# Photobooth-RasPI-Controller.net
KiCad netlist of a schematic drawn in EAGLE
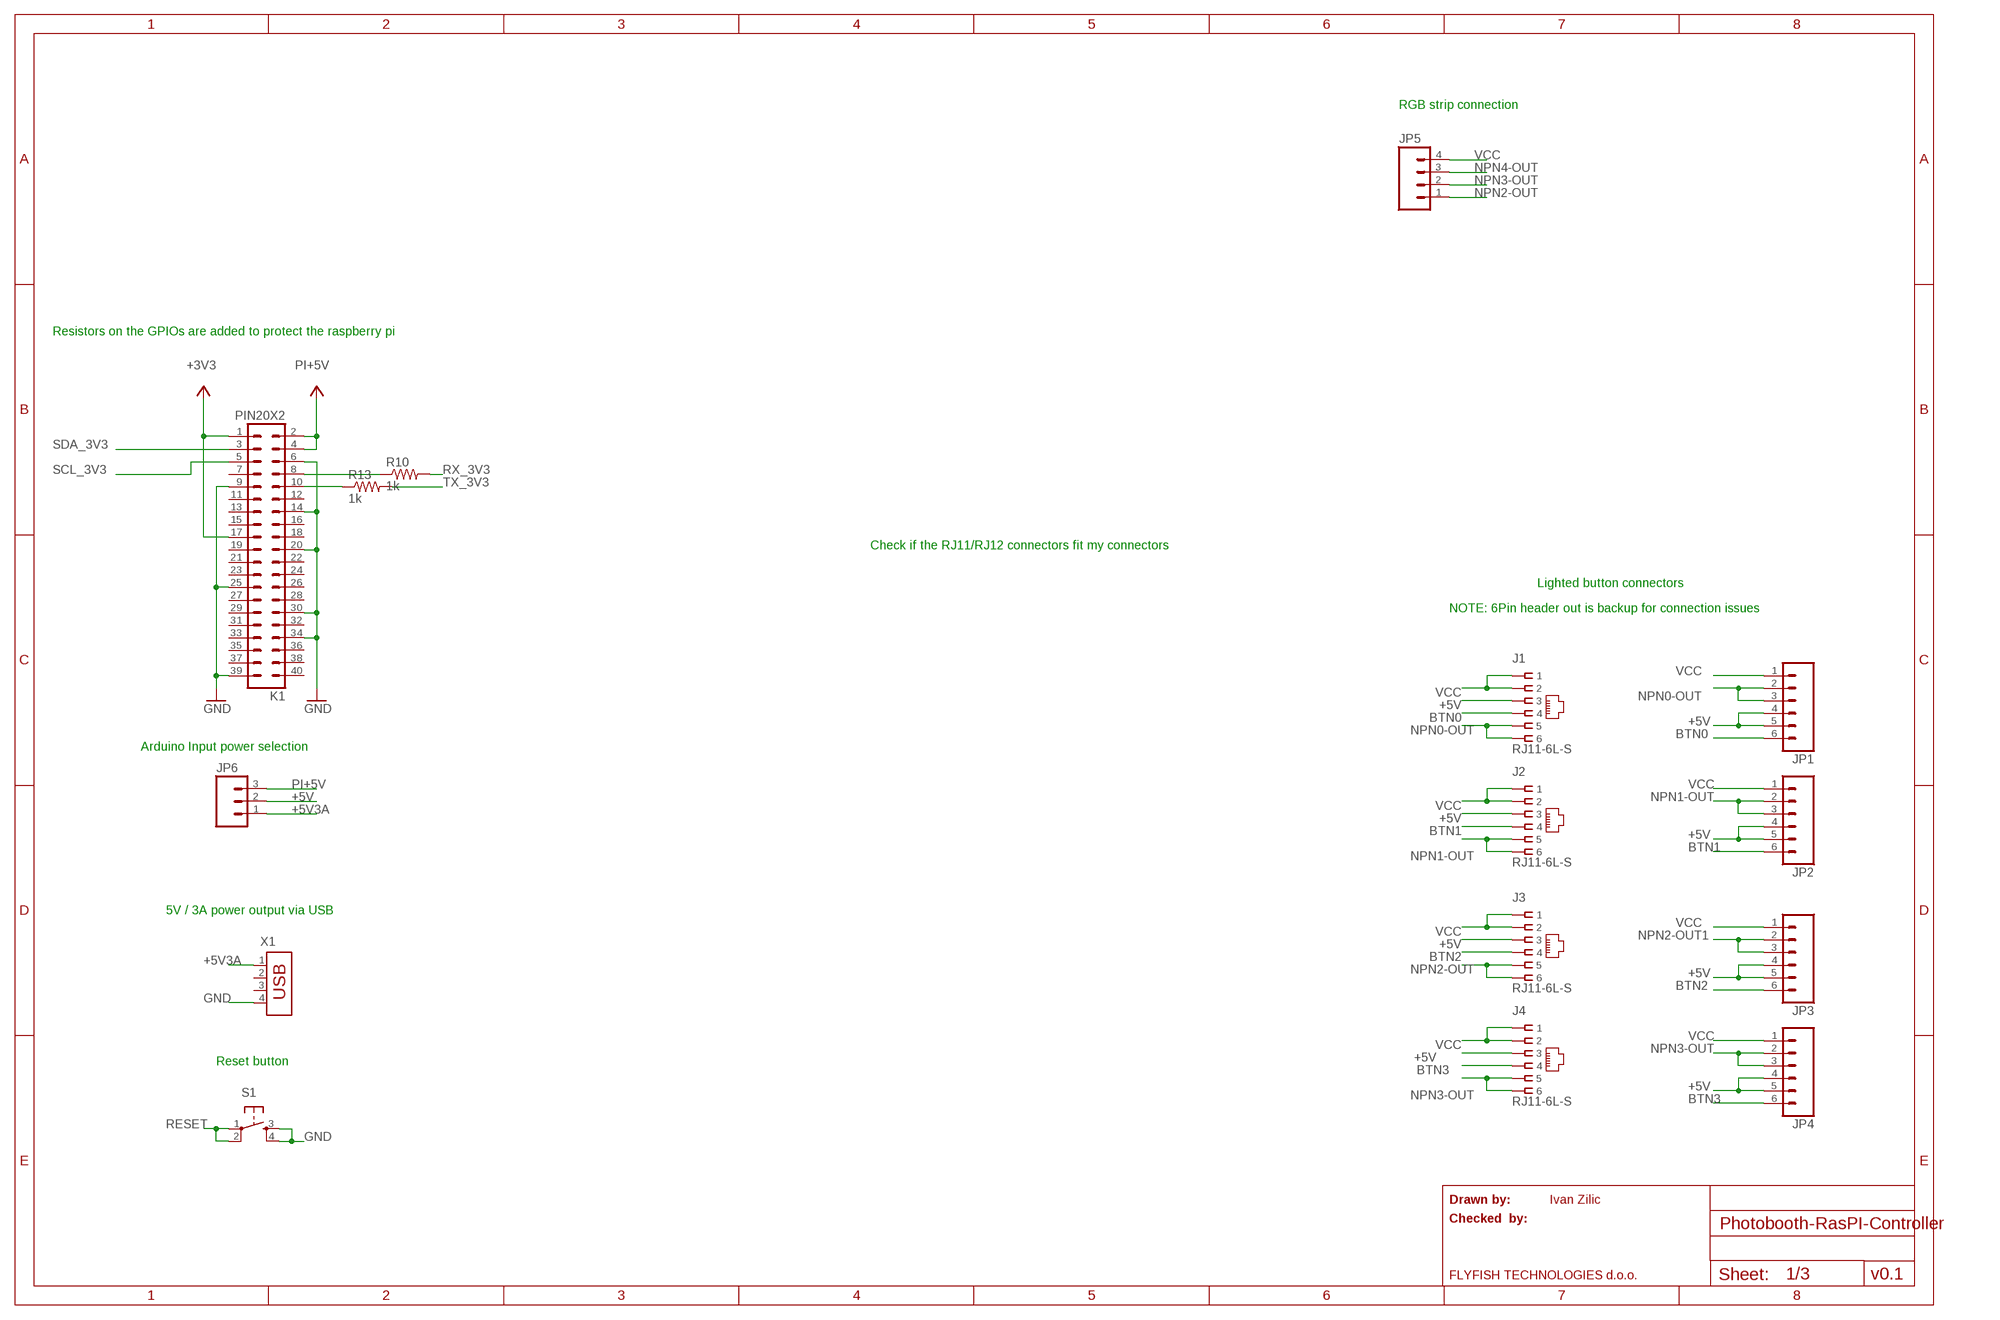
[diagram p0: schematic, sheet 1]
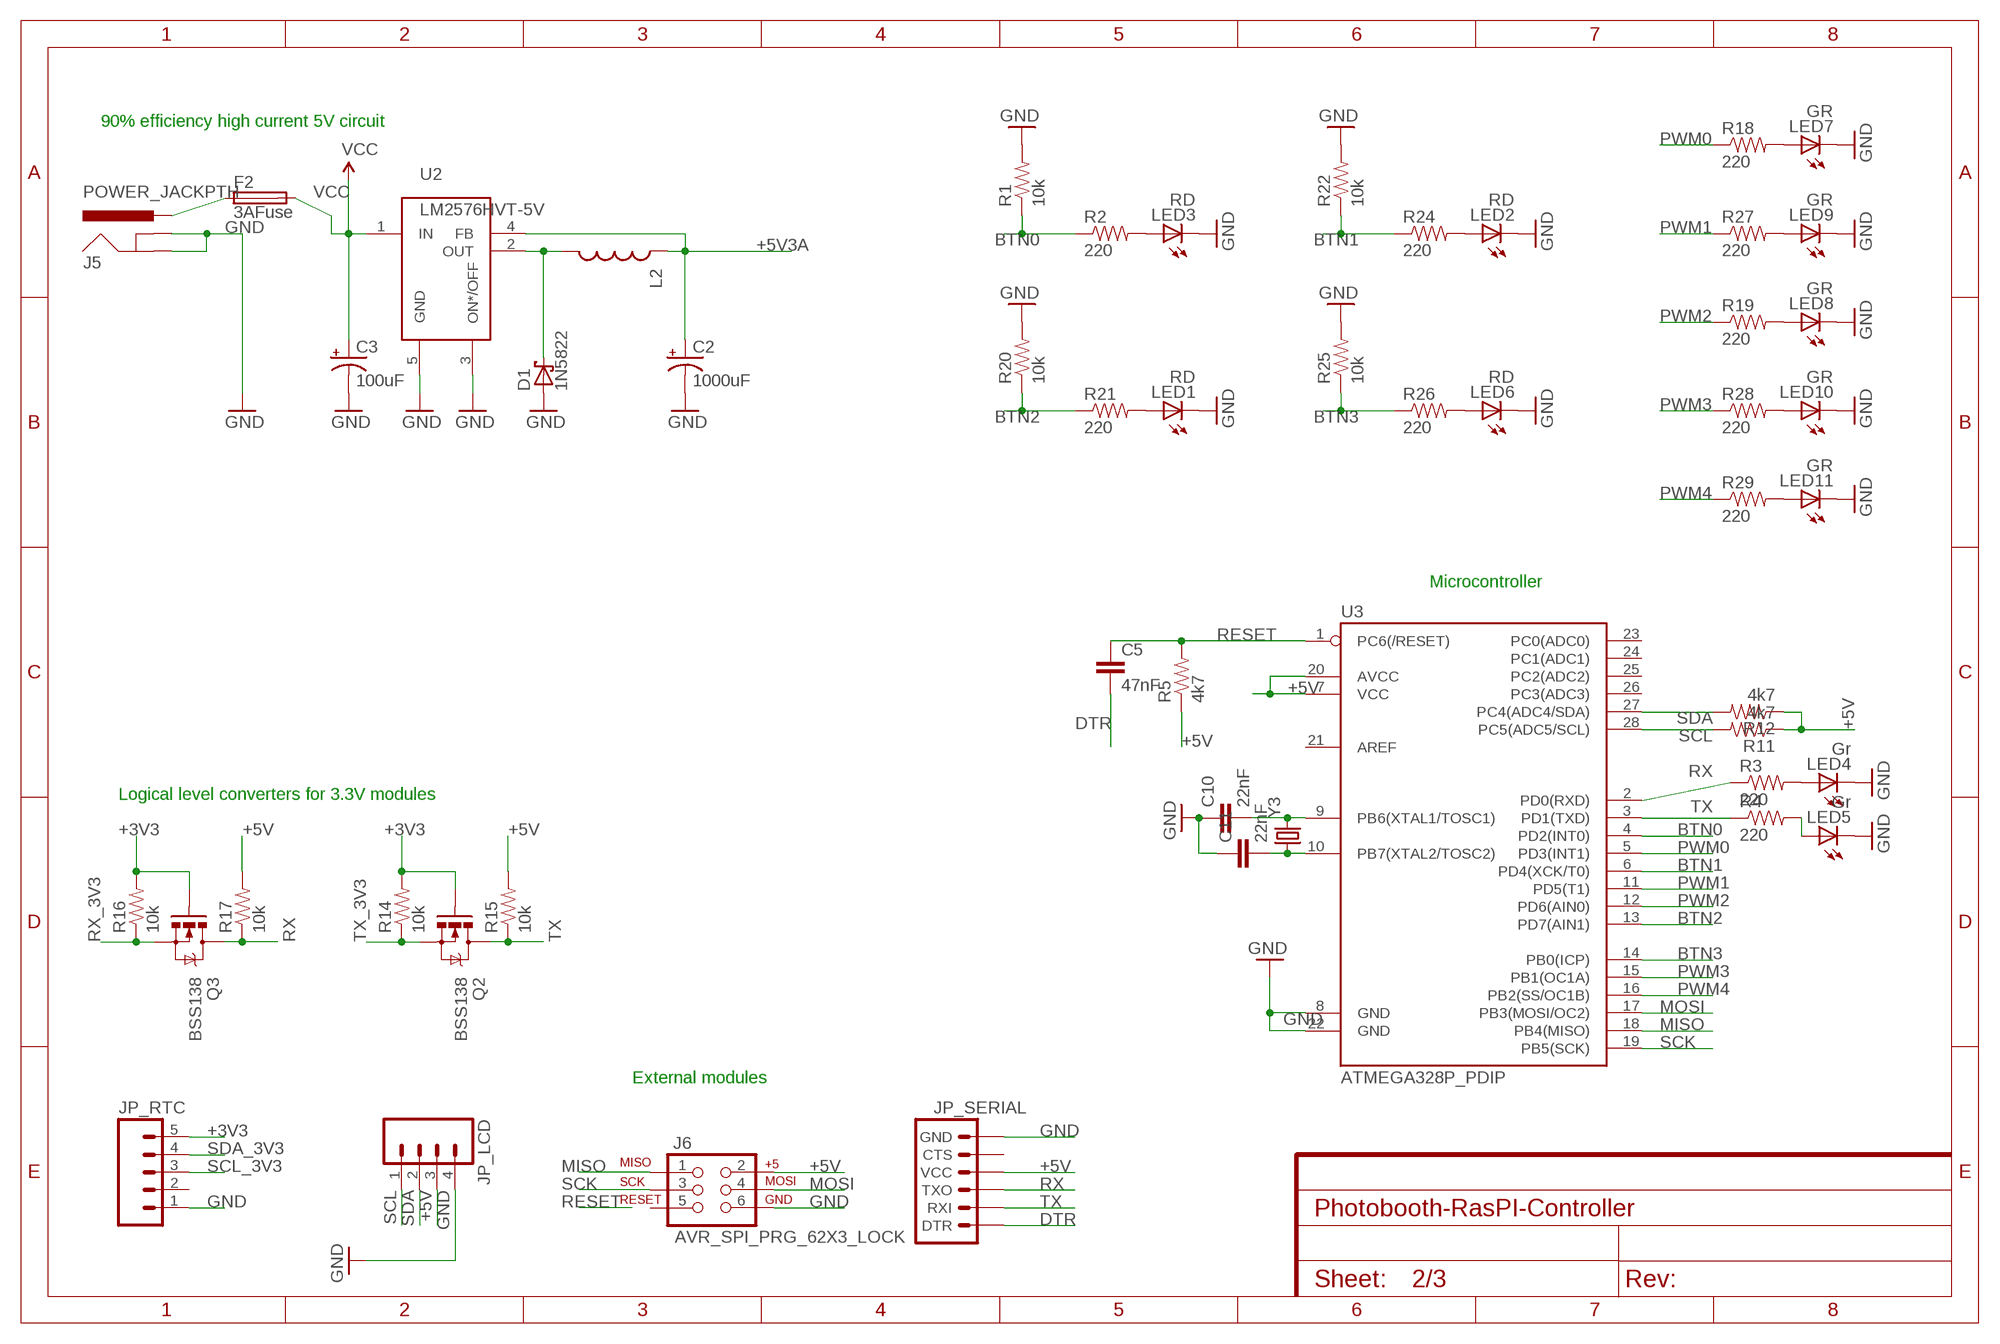
[diagram p1: schematic, sheet 2]
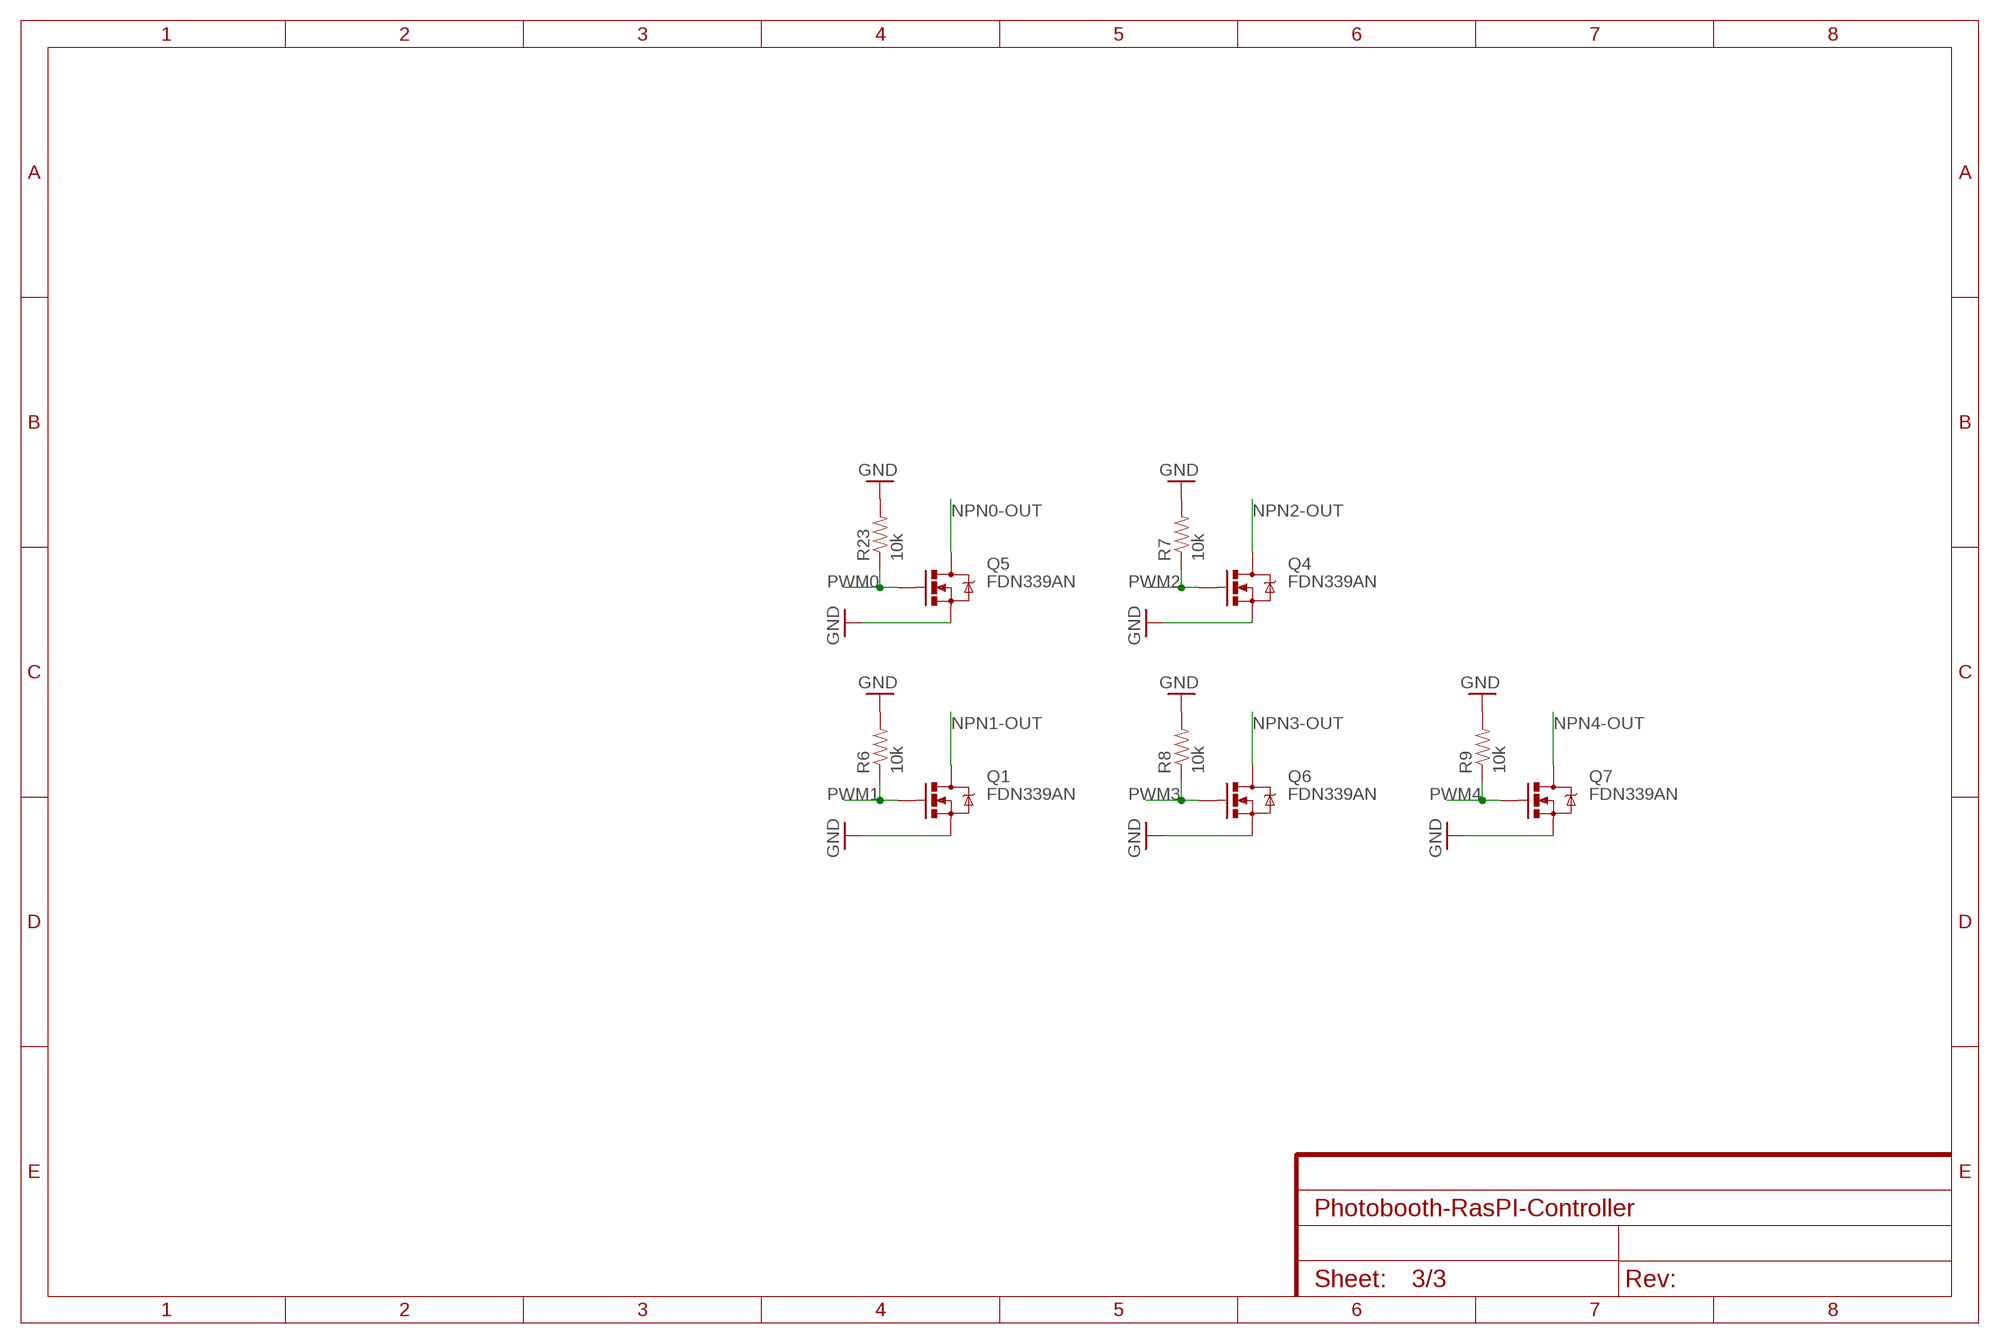
[diagram p2: schematic, sheet 3]

(export (version "E")
  (design (tool "Eeschema 10.0.6"))
  (components
    (comp (ref "Q1")
      (value "FDN339AN")
      (footprint "eagle-import:SOT23-3")
      (libsource (lib "eagle-import") (part "MOSFET-NCHANNELBSS138"))
    )
    (comp (ref "Q4")
      (value "FDN339AN")
      (footprint "eagle-import:SOT23-3")
      (libsource (lib "eagle-import") (part "MOSFET-NCHANNELBSS138"))
    )
    (comp (ref "Q5")
      (value "FDN339AN")
      (footprint "eagle-import:SOT23-3")
      (libsource (lib "eagle-import") (part "MOSFET-NCHANNELBSS138"))
    )
    (comp (ref "Q6")
      (value "FDN339AN")
      (footprint "eagle-import:SOT23-3")
      (libsource (lib "eagle-import") (part "MOSFET-NCHANNELBSS138"))
    )
    (comp (ref "Q7")
      (value "FDN339AN")
      (footprint "eagle-import:SOT23-3")
      (libsource (lib "eagle-import") (part "MOSFET-NCHANNELBSS138"))
    )
    (comp (ref "R6")
      (value "10k")
      (footprint "eagle-import:0805")
      (libsource (lib "eagle-import") (part "RESISTOR0805-RES"))
    )
    (comp (ref "R7")
      (value "10k")
      (footprint "eagle-import:0805")
      (libsource (lib "eagle-import") (part "RESISTOR0805-RES"))
    )
    (comp (ref "R8")
      (value "10k")
      (footprint "eagle-import:0805")
      (libsource (lib "eagle-import") (part "RESISTOR0805-RES"))
    )
    (comp (ref "R9")
      (value "10k")
      (footprint "eagle-import:0805")
      (libsource (lib "eagle-import") (part "RESISTOR0805-RES"))
    )
    (comp (ref "R23")
      (value "10k")
      (footprint "eagle-import:0805")
      (libsource (lib "eagle-import") (part "RESISTOR0805-RES"))
    )
    (comp (ref "J1")
      (value "RJ11-6L-S")
      (footprint "eagle-import:RJ11-NO_SHIELD")
      (fields (field (name "MF") "TYCO ELECTRONICS"))
      (libsource (lib "eagle-import") (part "RJ11-6L-S"))
    )
    (comp (ref "J2")
      (value "RJ11-6L-S")
      (footprint "eagle-import:RJ11-NO_SHIELD")
      (fields (field (name "MF") "TYCO ELECTRONICS"))
      (libsource (lib "eagle-import") (part "RJ11-6L-S"))
    )
    (comp (ref "J3")
      (value "RJ11-6L-S")
      (footprint "eagle-import:RJ11-NO_SHIELD")
      (fields (field (name "MF") "TYCO ELECTRONICS"))
      (libsource (lib "eagle-import") (part "RJ11-6L-S"))
    )
    (comp (ref "J4")
      (value "RJ11-6L-S")
      (footprint "eagle-import:RJ11-NO_SHIELD")
      (fields (field (name "MF") "TYCO ELECTRONICS"))
      (libsource (lib "eagle-import") (part "RJ11-6L-S"))
    )
    (comp (ref "JP1")
      (value "M06LOCK")
      (footprint "eagle-import:1X06_LOCK")
      (libsource (lib "eagle-import") (part "M06LOCK"))
    )
    (comp (ref "JP2")
      (value "M06LOCK")
      (footprint "eagle-import:1X06_LOCK")
      (libsource (lib "eagle-import") (part "M06LOCK"))
    )
    (comp (ref "JP3")
      (value "M06LOCK")
      (footprint "eagle-import:1X06_LOCK")
      (libsource (lib "eagle-import") (part "M06LOCK"))
    )
    (comp (ref "JP4")
      (value "M06LOCK")
      (footprint "eagle-import:1X06_LOCK")
      (libsource (lib "eagle-import") (part "M06LOCK"))
    )
    (comp (ref "JP5")
      (value "M04LOCK")
      (footprint "eagle-import:1X04_LOCK")
      (libsource (lib "eagle-import") (part "M04LOCK"))
    )
    (comp (ref "JP6")
      (value "M03LOCK")
      (footprint "eagle-import:1X03_LOCK")
      (libsource (lib "eagle-import") (part "M03LOCK"))
    )
    (comp (ref "K1")
      (value "PIN20X2")
      (footprint "eagle-import:PIN_20X2")
      (libsource (lib "eagle-import") (part "PIN20X2"))
    )
    (comp (ref "R10")
      (value "1k")
      (footprint "eagle-import:0805")
      (libsource (lib "eagle-import") (part "RESISTOR0805-RES"))
    )
    (comp (ref "R13")
      (value "1k")
      (footprint "eagle-import:0805")
      (libsource (lib "eagle-import") (part "RESISTOR0805-RES"))
    )
    (comp (ref "S1")
      (value "TAC_SWITCHPTH")
      (footprint "eagle-import:TACTILE-PTH")
      (libsource (lib "eagle-import") (part "TAC_SWITCHPTH"))
    )
    (comp (ref "X1")
      (value "USB-787616")
      (footprint "eagle-import:USB")
      (libsource (lib "eagle-import") (part "USB-787616"))
    )
    (comp (ref "C2")
      (value "1000uF")
      (footprint "eagle-import:CPOL-RADIAL-1000UF-25V")
      (libsource (lib "eagle-import") (part "1000UF-25V(PTH)"))
    )
    (comp (ref "C3")
      (value "100uF")
      (footprint "eagle-import:CPOL-RADIAL-100UF-25V")
      (libsource (lib "eagle-import") (part "CAP_POLPTH1"))
    )
    (comp (ref "C5")
      (value "47nF")
      (footprint "eagle-import:CAP-PTH-SMALL")
      (libsource (lib "eagle-import") (part "CAPPTH"))
    )
    (comp (ref "C10")
      (value "22nF")
      (footprint "eagle-import:CAP-PTH-SMALL")
      (libsource (lib "eagle-import") (part "CAPPTH"))
    )
    (comp (ref "C11")
      (value "22nF")
      (footprint "eagle-import:CAP-PTH-SMALL")
      (libsource (lib "eagle-import") (part "CAPPTH"))
    )
    (comp (ref "D1")
      (value "1N5822")
      (footprint "eagle-import:C4111-15")
      (libsource (lib "eagle-import") (part "1N5908"))
    )
    (comp (ref "F2")
      (value "3AFuse")
      (footprint "eagle-import:LITTLEFUSE")
      (libsource (lib "eagle-import") (part "LITTLEFUSE"))
    )
    (comp (ref "J5")
      (value "POWER_JACKPTH")
      (footprint "eagle-import:POWER_JACK_PTH")
      (libsource (lib "eagle-import") (part "POWER_JACKPTH"))
    )
    (comp (ref "J6")
      (value "AVR_SPI_PRG_62X3_LOCK")
      (footprint "eagle-import:2X3_LOCK")
      (libsource (lib "eagle-import") (part "AVR_SPI_PRG_62X3_LOCK"))
    )
    (comp (ref "JP_LCD")
      (value "M04PTH")
      (footprint "eagle-import:1X04")
      (libsource (lib "eagle-import") (part "M04PTH"))
    )
    (comp (ref "JP_RTC")
      (value "M05LOCK")
      (footprint "eagle-import:1X05_LOCK")
      (libsource (lib "eagle-import") (part "M05LOCK"))
    )
    (comp (ref "JP_SERIAL")
      (value "ARDUINO_SERIAL_PROGRAMLOCK")
      (footprint "eagle-import:1X06_LOCK")
      (libsource (lib "eagle-import") (part "ARDUINO_SERIAL_PROGRAMLOCK"))
    )
    (comp (ref "L2")
      (value "INDUCTORRLB0912")
      (footprint "eagle-import:RLB0912")
      (libsource (lib "eagle-import") (part "INDUCTORRLB0912"))
    )
    (comp (ref "LED1")
      (value "RD")
      (footprint "eagle-import:CHIP-LED0805")
      (libsource (lib "eagle-import") (part "LEDCHIP-LED0805"))
    )
    (comp (ref "LED2")
      (value "RD")
      (footprint "eagle-import:CHIP-LED0805")
      (libsource (lib "eagle-import") (part "LEDCHIP-LED0805"))
    )
    (comp (ref "LED3")
      (value "RD")
      (footprint "eagle-import:CHIP-LED0805")
      (libsource (lib "eagle-import") (part "LEDCHIP-LED0805"))
    )
    (comp (ref "LED4")
      (value "Gr")
      (footprint "eagle-import:CHIP-LED0805")
      (libsource (lib "eagle-import") (part "LEDCHIP-LED0805"))
    )
    (comp (ref "LED5")
      (value "Gr")
      (footprint "eagle-import:CHIP-LED0805")
      (libsource (lib "eagle-import") (part "LEDCHIP-LED0805"))
    )
    (comp (ref "LED6")
      (value "RD")
      (footprint "eagle-import:CHIP-LED0805")
      (libsource (lib "eagle-import") (part "LEDCHIP-LED0805"))
    )
    (comp (ref "LED7")
      (value "GR")
      (footprint "eagle-import:CHIP-LED0805")
      (libsource (lib "eagle-import") (part "LEDCHIP-LED0805"))
    )
    (comp (ref "LED8")
      (value "GR")
      (footprint "eagle-import:CHIP-LED0805")
      (libsource (lib "eagle-import") (part "LEDCHIP-LED0805"))
    )
    (comp (ref "LED9")
      (value "GR")
      (footprint "eagle-import:CHIP-LED0805")
      (libsource (lib "eagle-import") (part "LEDCHIP-LED0805"))
    )
    (comp (ref "LED10")
      (value "GR")
      (footprint "eagle-import:CHIP-LED0805")
      (libsource (lib "eagle-import") (part "LEDCHIP-LED0805"))
    )
    (comp (ref "LED11")
      (value "GR")
      (footprint "eagle-import:CHIP-LED0805")
      (libsource (lib "eagle-import") (part "LEDCHIP-LED0805"))
    )
    (comp (ref "Q2")
      (value "BSS138")
      (footprint "eagle-import:SOT23-3")
      (libsource (lib "eagle-import") (part "MOSFET-NCHANNELBSS138"))
    )
    (comp (ref "Q3")
      (value "BSS138")
      (footprint "eagle-import:SOT23-3")
      (libsource (lib "eagle-import") (part "MOSFET-NCHANNELBSS138"))
    )
    (comp (ref "R1")
      (value "10k")
      (footprint "eagle-import:0805")
      (libsource (lib "eagle-import") (part "RESISTOR0805-RES"))
    )
    (comp (ref "R2")
      (value "220")
      (footprint "eagle-import:0805")
      (libsource (lib "eagle-import") (part "RESISTOR0805-RES"))
    )
    (comp (ref "R3")
      (value "220")
      (footprint "eagle-import:0805")
      (libsource (lib "eagle-import") (part "RESISTOR0805-RES"))
    )
    (comp (ref "R4")
      (value "220")
      (footprint "eagle-import:0805")
      (libsource (lib "eagle-import") (part "RESISTOR0805-RES"))
    )
    (comp (ref "R5")
      (value "4k7")
      (footprint "eagle-import:0805")
      (libsource (lib "eagle-import") (part "RESISTOR0805-RES"))
    )
    (comp (ref "R11")
      (value "4k7")
      (footprint "eagle-import:0805")
      (libsource (lib "eagle-import") (part "RESISTOR0805-RES"))
    )
    (comp (ref "R12")
      (value "4k7")
      (footprint "eagle-import:0805")
      (libsource (lib "eagle-import") (part "RESISTOR0805-RES"))
    )
    (comp (ref "R14")
      (value "10k")
      (footprint "eagle-import:0805")
      (libsource (lib "eagle-import") (part "RESISTOR0805-RES"))
    )
    (comp (ref "R15")
      (value "10k")
      (footprint "eagle-import:0805")
      (libsource (lib "eagle-import") (part "RESISTOR0805-RES"))
    )
    (comp (ref "R16")
      (value "10k")
      (footprint "eagle-import:0805")
      (libsource (lib "eagle-import") (part "RESISTOR0805-RES"))
    )
    (comp (ref "R17")
      (value "10k")
      (footprint "eagle-import:0805")
      (libsource (lib "eagle-import") (part "RESISTOR0805-RES"))
    )
    (comp (ref "R18")
      (value "220")
      (footprint "eagle-import:0805")
      (libsource (lib "eagle-import") (part "RESISTOR0805-RES"))
    )
    (comp (ref "R19")
      (value "220")
      (footprint "eagle-import:0805")
      (libsource (lib "eagle-import") (part "RESISTOR0805-RES"))
    )
    (comp (ref "R20")
      (value "10k")
      (footprint "eagle-import:0805")
      (libsource (lib "eagle-import") (part "RESISTOR0805-RES"))
    )
    (comp (ref "R21")
      (value "220")
      (footprint "eagle-import:0805")
      (libsource (lib "eagle-import") (part "RESISTOR0805-RES"))
    )
    (comp (ref "R22")
      (value "10k")
      (footprint "eagle-import:0805")
      (libsource (lib "eagle-import") (part "RESISTOR0805-RES"))
    )
    (comp (ref "R24")
      (value "220")
      (footprint "eagle-import:0805")
      (libsource (lib "eagle-import") (part "RESISTOR0805-RES"))
    )
    (comp (ref "R25")
      (value "10k")
      (footprint "eagle-import:0805")
      (libsource (lib "eagle-import") (part "RESISTOR0805-RES"))
    )
    (comp (ref "R26")
      (value "220")
      (footprint "eagle-import:0805")
      (libsource (lib "eagle-import") (part "RESISTOR0805-RES"))
    )
    (comp (ref "R27")
      (value "220")
      (footprint "eagle-import:0805")
      (libsource (lib "eagle-import") (part "RESISTOR0805-RES"))
    )
    (comp (ref "R28")
      (value "220")
      (footprint "eagle-import:0805")
      (libsource (lib "eagle-import") (part "RESISTOR0805-RES"))
    )
    (comp (ref "R29")
      (value "220")
      (footprint "eagle-import:0805")
      (libsource (lib "eagle-import") (part "RESISTOR0805-RES"))
    )
    (comp (ref "U2")
      (value "LM2576HVT-5V")
      (footprint "eagle-import:LM2576")
      (libsource (lib "eagle-import") (part "LM2576"))
    )
    (comp (ref "U3")
      (value "ATMEGA328P_PDIP")
      (footprint "eagle-import:DIL28-3")
      (libsource (lib "eagle-import") (part "ATMEGA328P_PDIP"))
    )
    (comp (ref "Y3")
      (value "CRYSTALHC49UV")
      (footprint "eagle-import:HC49U-V")
      (libsource (lib "eagle-import") (part "CRYSTALHC49UV"))
    )
  )
  (nets
    (net (code "1") (name "+3V3") (class "Default")
      (node (ref "JP_RTC") (pin "5") (pinfunction "5_5") (pintype "passive"))
      (node (ref "K1") (pin "1") (pinfunction "1_1") (pintype "passive"))
      (node (ref "K1") (pin "17") (pinfunction "17_17") (pintype "passive"))
      (node (ref "Q2") (pin "1") (pinfunction "G_1") (pintype "passive"))
      (node (ref "Q3") (pin "1") (pinfunction "G_1") (pintype "passive"))
      (node (ref "R14") (pin "2") (pinfunction "2_2") (pintype "passive"))
      (node (ref "R16") (pin "2") (pinfunction "2_2") (pintype "passive"))
    )
    (net (code "2") (name "+5V") (class "Default")
      (node (ref "J1") (pin "3") (pinfunction "3_3") (pintype "passive"))
      (node (ref "J2") (pin "3") (pinfunction "3_3") (pintype "passive"))
      (node (ref "J3") (pin "3") (pinfunction "3_3") (pintype "passive"))
      (node (ref "J4") (pin "3") (pinfunction "3_3") (pintype "passive"))
      (node (ref "J6") (pin "2") (pinfunction "2_2") (pintype "passive"))
      (node (ref "JP1") (pin "4") (pinfunction "4_4") (pintype "passive"))
      (node (ref "JP1") (pin "5") (pinfunction "5_5") (pintype "passive"))
      (node (ref "JP2") (pin "4") (pinfunction "4_4") (pintype "passive"))
      (node (ref "JP2") (pin "5") (pinfunction "5_5") (pintype "passive"))
      (node (ref "JP3") (pin "4") (pinfunction "4_4") (pintype "passive"))
      (node (ref "JP3") (pin "5") (pinfunction "5_5") (pintype "passive"))
      (node (ref "JP4") (pin "4") (pinfunction "4_4") (pintype "passive"))
      (node (ref "JP4") (pin "5") (pinfunction "5_5") (pintype "passive"))
      (node (ref "JP6") (pin "2") (pinfunction "2_2") (pintype "passive"))
      (node (ref "JP_LCD") (pin "3") (pinfunction "3_3") (pintype "passive"))
      (node (ref "JP_SERIAL") (pin "4") (pinfunction "VCC_4") (pintype "passive"))
      (node (ref "R11") (pin "1") (pinfunction "1_1") (pintype "passive"))
      (node (ref "R12") (pin "1") (pinfunction "1_1") (pintype "passive"))
      (node (ref "R15") (pin "2") (pinfunction "2_2") (pintype "passive"))
      (node (ref "R17") (pin "2") (pinfunction "2_2") (pintype "passive"))
      (node (ref "R5") (pin "1") (pinfunction "1_1") (pintype "passive"))
      (node (ref "U3") (pin "20") (pinfunction "AVCC_20") (pintype "bidirectional"))
      (node (ref "U3") (pin "7") (pinfunction "VCC_7") (pintype "bidirectional"))
    )
    (net (code "3") (name "+5V3A") (class "Default")
      (node (ref "C2") (pin "+") (pinfunction "+_+") (pintype "passive"))
      (node (ref "JP6") (pin "1") (pinfunction "1_1") (pintype "passive"))
      (node (ref "L2") (pin "1") (pinfunction "1_1") (pintype "passive"))
      (node (ref "U2") (pin "4") (pinfunction "FB_4") (pintype "bidirectional"))
      (node (ref "X1") (pin "1") (pinfunction "1_1") (pintype "passive"))
    )
    (net (code "4") (name "BTN0") (class "Default")
      (node (ref "J1") (pin "4") (pinfunction "4_4") (pintype "passive"))
      (node (ref "JP1") (pin "6") (pinfunction "6_6") (pintype "passive"))
      (node (ref "R1") (pin "1") (pinfunction "1_1") (pintype "passive"))
      (node (ref "R2") (pin "1") (pinfunction "1_1") (pintype "passive"))
      (node (ref "U3") (pin "4") (pinfunction "PD2(INT0)_4") (pintype "bidirectional"))
    )
    (net (code "5") (name "BTN1") (class "Default")
      (node (ref "J2") (pin "4") (pinfunction "4_4") (pintype "passive"))
      (node (ref "JP2") (pin "6") (pinfunction "6_6") (pintype "passive"))
      (node (ref "R22") (pin "1") (pinfunction "1_1") (pintype "passive"))
      (node (ref "R24") (pin "1") (pinfunction "1_1") (pintype "passive"))
      (node (ref "U3") (pin "6") (pinfunction "PD4(XCK/T0)_6") (pintype "bidirectional"))
    )
    (net (code "6") (name "BTN2") (class "Default")
      (node (ref "J3") (pin "4") (pinfunction "4_4") (pintype "passive"))
      (node (ref "JP3") (pin "6") (pinfunction "6_6") (pintype "passive"))
      (node (ref "R20") (pin "1") (pinfunction "1_1") (pintype "passive"))
      (node (ref "R21") (pin "1") (pinfunction "1_1") (pintype "passive"))
      (node (ref "U3") (pin "13") (pinfunction "PD7(AIN1)_13") (pintype "bidirectional"))
    )
    (net (code "7") (name "BTN3") (class "Default")
      (node (ref "J4") (pin "4") (pinfunction "4_4") (pintype "passive"))
      (node (ref "JP4") (pin "6") (pinfunction "6_6") (pintype "passive"))
      (node (ref "R25") (pin "1") (pinfunction "1_1") (pintype "passive"))
      (node (ref "R26") (pin "1") (pinfunction "1_1") (pintype "passive"))
      (node (ref "U3") (pin "14") (pinfunction "PB0(ICP)_14") (pintype "bidirectional"))
    )
    (net (code "8") (name "DTR") (class "Default")
      (node (ref "C5") (pin "2") (pinfunction "2_2") (pintype "passive"))
      (node (ref "JP_SERIAL") (pin "1") (pinfunction "DTR_1") (pintype "passive"))
    )
    (net (code "9") (name "GND") (class "Default")
      (node (ref "C10") (pin "1") (pinfunction "1_1") (pintype "passive"))
      (node (ref "C11") (pin "1") (pinfunction "1_1") (pintype "passive"))
      (node (ref "C2") (pin "-") (pinfunction "-_-") (pintype "passive"))
      (node (ref "C3") (pin "2") (pinfunction "-_2") (pintype "passive"))
      (node (ref "D1") (pin "A") (pinfunction "A_A") (pintype "passive"))
      (node (ref "J5") (pin "GND") (pinfunction "GND_GND") (pintype "bidirectional"))
      (node (ref "J5") (pin "GNDBREAK") (pinfunction "GNDBREAK_GNDBREAK") (pintype "bidirectional"))
      (node (ref "J6") (pin "6") (pinfunction "6_6") (pintype "passive"))
      (node (ref "JP_LCD") (pin "4") (pinfunction "4_4") (pintype "passive"))
      (node (ref "JP_RTC") (pin "1") (pinfunction "1_1") (pintype "passive"))
      (node (ref "JP_SERIAL") (pin "6") (pinfunction "GND_6") (pintype "passive"))
      (node (ref "K1") (pin "14") (pinfunction "14_14") (pintype "passive"))
      (node (ref "K1") (pin "20") (pinfunction "20_20") (pintype "passive"))
      (node (ref "K1") (pin "25") (pinfunction "25_25") (pintype "passive"))
      (node (ref "K1") (pin "30") (pinfunction "30_30") (pintype "passive"))
      (node (ref "K1") (pin "34") (pinfunction "34_34") (pintype "passive"))
      (node (ref "K1") (pin "39") (pinfunction "39_39") (pintype "passive"))
      (node (ref "K1") (pin "6") (pinfunction "6_6") (pintype "passive"))
      (node (ref "K1") (pin "9") (pinfunction "9_9") (pintype "passive"))
      (node (ref "LED1") (pin "C") (pinfunction "C_C") (pintype "passive"))
      (node (ref "LED10") (pin "C") (pinfunction "C_C") (pintype "passive"))
      (node (ref "LED11") (pin "C") (pinfunction "C_C") (pintype "passive"))
      (node (ref "LED2") (pin "C") (pinfunction "C_C") (pintype "passive"))
      (node (ref "LED3") (pin "C") (pinfunction "C_C") (pintype "passive"))
      (node (ref "LED4") (pin "C") (pinfunction "C_C") (pintype "passive"))
      (node (ref "LED5") (pin "C") (pinfunction "C_C") (pintype "passive"))
      (node (ref "LED6") (pin "C") (pinfunction "C_C") (pintype "passive"))
      (node (ref "LED7") (pin "C") (pinfunction "C_C") (pintype "passive"))
      (node (ref "LED8") (pin "C") (pinfunction "C_C") (pintype "passive"))
      (node (ref "LED9") (pin "C") (pinfunction "C_C") (pintype "passive"))
      (node (ref "Q1") (pin "2") (pinfunction "S_2") (pintype "passive"))
      (node (ref "Q4") (pin "2") (pinfunction "S_2") (pintype "passive"))
      (node (ref "Q5") (pin "2") (pinfunction "S_2") (pintype "passive"))
      (node (ref "Q6") (pin "2") (pinfunction "S_2") (pintype "passive"))
      (node (ref "Q7") (pin "2") (pinfunction "S_2") (pintype "passive"))
      (node (ref "R1") (pin "2") (pinfunction "2_2") (pintype "passive"))
      (node (ref "R20") (pin "2") (pinfunction "2_2") (pintype "passive"))
      (node (ref "R22") (pin "2") (pinfunction "2_2") (pintype "passive"))
      (node (ref "R23") (pin "2") (pinfunction "2_2") (pintype "passive"))
      (node (ref "R25") (pin "2") (pinfunction "2_2") (pintype "passive"))
      (node (ref "R6") (pin "2") (pinfunction "2_2") (pintype "passive"))
      (node (ref "R7") (pin "2") (pinfunction "2_2") (pintype "passive"))
      (node (ref "R8") (pin "2") (pinfunction "2_2") (pintype "passive"))
      (node (ref "R9") (pin "2") (pinfunction "2_2") (pintype "passive"))
      (node (ref "S1") (pin "3") (pinfunction "3_3") (pintype "passive"))
      (node (ref "S1") (pin "4") (pinfunction "4_4") (pintype "passive"))
      (node (ref "U2") (pin "3") (pinfunction "ON*/OFF_3") (pintype "bidirectional"))
      (node (ref "U2") (pin "5") (pinfunction "GND_5") (pintype "bidirectional"))
      (node (ref "U3") (pin "22") (pinfunction "GND_22") (pintype "bidirectional"))
      (node (ref "U3") (pin "8") (pinfunction "GND_8") (pintype "bidirectional"))
      (node (ref "X1") (pin "4") (pinfunction "4_4") (pintype "passive"))
    )
    (net (code "10") (name "MISO") (class "Default")
      (node (ref "J6") (pin "1") (pinfunction "1_1") (pintype "passive"))
      (node (ref "U3") (pin "18") (pinfunction "PB4(MISO)_18") (pintype "bidirectional"))
    )
    (net (code "11") (name "MOSI") (class "Default")
      (node (ref "J6") (pin "4") (pinfunction "4_4") (pintype "passive"))
      (node (ref "U3") (pin "17") (pinfunction "PB3(MOSI/OC2)_17") (pintype "bidirectional"))
    )
    (net (code "12") (name "NPN0-OUT") (class "Default")
      (node (ref "J1") (pin "5") (pinfunction "5_5") (pintype "passive"))
      (node (ref "J1") (pin "6") (pinfunction "6_6") (pintype "passive"))
      (node (ref "JP1") (pin "2") (pinfunction "2_2") (pintype "passive"))
      (node (ref "JP1") (pin "3") (pinfunction "3_3") (pintype "passive"))
      (node (ref "Q5") (pin "3") (pinfunction "D_3") (pintype "passive"))
    )
    (net (code "13") (name "NPN1-OUT") (class "Default")
      (node (ref "J2") (pin "5") (pinfunction "5_5") (pintype "passive"))
      (node (ref "J2") (pin "6") (pinfunction "6_6") (pintype "passive"))
      (node (ref "JP2") (pin "2") (pinfunction "2_2") (pintype "passive"))
      (node (ref "JP2") (pin "3") (pinfunction "3_3") (pintype "passive"))
      (node (ref "Q1") (pin "3") (pinfunction "D_3") (pintype "passive"))
    )
    (net (code "14") (name "NPN2-OUT") (class "Default")
      (node (ref "J3") (pin "5") (pinfunction "5_5") (pintype "passive"))
      (node (ref "J3") (pin "6") (pinfunction "6_6") (pintype "passive"))
      (node (ref "JP5") (pin "1") (pinfunction "1_1") (pintype "passive"))
      (node (ref "Q4") (pin "3") (pinfunction "D_3") (pintype "passive"))
    )
    (net (code "15") (name "NPN2-OUT1") (class "Default")
      (node (ref "JP3") (pin "2") (pinfunction "2_2") (pintype "passive"))
      (node (ref "JP3") (pin "3") (pinfunction "3_3") (pintype "passive"))
    )
    (net (code "16") (name "NPN3-OUT") (class "Default")
      (node (ref "J4") (pin "5") (pinfunction "5_5") (pintype "passive"))
      (node (ref "J4") (pin "6") (pinfunction "6_6") (pintype "passive"))
      (node (ref "JP4") (pin "2") (pinfunction "2_2") (pintype "passive"))
      (node (ref "JP4") (pin "3") (pinfunction "3_3") (pintype "passive"))
      (node (ref "JP5") (pin "2") (pinfunction "2_2") (pintype "passive"))
      (node (ref "Q6") (pin "3") (pinfunction "D_3") (pintype "passive"))
    )
    (net (code "17") (name "NPN4-OUT") (class "Default")
      (node (ref "JP5") (pin "3") (pinfunction "3_3") (pintype "passive"))
      (node (ref "Q7") (pin "3") (pinfunction "D_3") (pintype "passive"))
    )
    (net (code "18") (name "Net-(F2-Pad1)") (class "Default")
      (node (ref "F2") (pin "1") (pinfunction "1_1") (pintype "passive"))
      (node (ref "J5") (pin "PWR") (pinfunction "PWR_PWR") (pintype "bidirectional"))
    )
    (net (code "19") (name "Net-(K1-Pad8)") (class "Default")
      (node (ref "K1") (pin "8") (pinfunction "8_8") (pintype "passive"))
      (node (ref "R10") (pin "1") (pinfunction "1_1") (pintype "passive"))
    )
    (net (code "20") (name "Net-(K1-Pad10)") (class "Default")
      (node (ref "K1") (pin "10") (pinfunction "10_10") (pintype "passive"))
      (node (ref "R13") (pin "1") (pinfunction "1_1") (pintype "passive"))
    )
    (net (code "21") (name "Net-(LED1-PadA)") (class "Default")
      (node (ref "LED1") (pin "A") (pinfunction "A_A") (pintype "passive"))
      (node (ref "R21") (pin "2") (pinfunction "2_2") (pintype "passive"))
    )
    (net (code "22") (name "Net-(LED2-PadA)") (class "Default")
      (node (ref "LED2") (pin "A") (pinfunction "A_A") (pintype "passive"))
      (node (ref "R24") (pin "2") (pinfunction "2_2") (pintype "passive"))
    )
    (net (code "23") (name "Net-(LED3-PadA)") (class "Default")
      (node (ref "LED3") (pin "A") (pinfunction "A_A") (pintype "passive"))
      (node (ref "R2") (pin "2") (pinfunction "2_2") (pintype "passive"))
    )
    (net (code "24") (name "Net-(LED4-PadA)") (class "Default")
      (node (ref "LED4") (pin "A") (pinfunction "A_A") (pintype "passive"))
      (node (ref "R3") (pin "2") (pinfunction "2_2") (pintype "passive"))
    )
    (net (code "25") (name "Net-(LED5-PadA)") (class "Default")
      (node (ref "LED5") (pin "A") (pinfunction "A_A") (pintype "passive"))
      (node (ref "R4") (pin "2") (pinfunction "2_2") (pintype "passive"))
    )
    (net (code "26") (name "Net-(LED6-PadA)") (class "Default")
      (node (ref "LED6") (pin "A") (pinfunction "A_A") (pintype "passive"))
      (node (ref "R26") (pin "2") (pinfunction "2_2") (pintype "passive"))
    )
    (net (code "27") (name "Net-(LED7-PadA)") (class "Default")
      (node (ref "LED7") (pin "A") (pinfunction "A_A") (pintype "passive"))
      (node (ref "R18") (pin "2") (pinfunction "2_2") (pintype "passive"))
    )
    (net (code "28") (name "Net-(LED8-PadA)") (class "Default")
      (node (ref "LED8") (pin "A") (pinfunction "A_A") (pintype "passive"))
      (node (ref "R19") (pin "2") (pinfunction "2_2") (pintype "passive"))
    )
    (net (code "29") (name "Net-(LED9-PadA)") (class "Default")
      (node (ref "LED9") (pin "A") (pinfunction "A_A") (pintype "passive"))
      (node (ref "R27") (pin "2") (pinfunction "2_2") (pintype "passive"))
    )
    (net (code "30") (name "Net-(LED10-PadA)") (class "Default")
      (node (ref "LED10") (pin "A") (pinfunction "A_A") (pintype "passive"))
      (node (ref "R28") (pin "2") (pinfunction "2_2") (pintype "passive"))
    )
    (net (code "31") (name "Net-(LED11-PadA)") (class "Default")
      (node (ref "LED11") (pin "A") (pinfunction "A_A") (pintype "passive"))
      (node (ref "R29") (pin "2") (pinfunction "2_2") (pintype "passive"))
    )
    (net (code "32") (name "Net-(U2-OUT)") (class "Default")
      (node (ref "D1") (pin "C") (pinfunction "C_C") (pintype "passive"))
      (node (ref "L2") (pin "2") (pinfunction "2_2") (pintype "passive"))
      (node (ref "U2") (pin "2") (pinfunction "OUT_2") (pintype "bidirectional"))
    )
    (net (code "33") (name "Net-(U3-PB6(XTAL1{slash}TOSC1))") (class "Default")
      (node (ref "C10") (pin "2") (pinfunction "2_2") (pintype "passive"))
      (node (ref "U3") (pin "9") (pinfunction "PB6(XTAL1/TOSC1)_9") (pintype "bidirectional"))
      (node (ref "Y3") (pin "2") (pinfunction "2_2") (pintype "passive"))
    )
    (net (code "34") (name "Net-(U3-PB7(XTAL2{slash}TOSC2))") (class "Default")
      (node (ref "C11") (pin "2") (pinfunction "2_2") (pintype "passive"))
      (node (ref "U3") (pin "10") (pinfunction "PB7(XTAL2/TOSC2)_10") (pintype "bidirectional"))
      (node (ref "Y3") (pin "1") (pinfunction "1_1") (pintype "passive"))
    )
    (net (code "35") (name "PI+5V") (class "Default")
      (node (ref "JP6") (pin "3") (pinfunction "3_3") (pintype "passive"))
      (node (ref "K1") (pin "2") (pinfunction "2_2") (pintype "passive"))
      (node (ref "K1") (pin "4") (pinfunction "4_4") (pintype "passive"))
    )
    (net (code "36") (name "PWM0") (class "Default")
      (node (ref "Q5") (pin "1") (pinfunction "G_1") (pintype "passive"))
      (node (ref "R18") (pin "1") (pinfunction "1_1") (pintype "passive"))
      (node (ref "R23") (pin "1") (pinfunction "1_1") (pintype "passive"))
      (node (ref "U3") (pin "5") (pinfunction "PD3(INT1)_5") (pintype "bidirectional"))
    )
    (net (code "37") (name "PWM1") (class "Default")
      (node (ref "Q1") (pin "1") (pinfunction "G_1") (pintype "passive"))
      (node (ref "R27") (pin "1") (pinfunction "1_1") (pintype "passive"))
      (node (ref "R6") (pin "1") (pinfunction "1_1") (pintype "passive"))
      (node (ref "U3") (pin "11") (pinfunction "PD5(T1)_11") (pintype "bidirectional"))
    )
    (net (code "38") (name "PWM2") (class "Default")
      (node (ref "Q4") (pin "1") (pinfunction "G_1") (pintype "passive"))
      (node (ref "R19") (pin "1") (pinfunction "1_1") (pintype "passive"))
      (node (ref "R7") (pin "1") (pinfunction "1_1") (pintype "passive"))
      (node (ref "U3") (pin "12") (pinfunction "PD6(AIN0)_12") (pintype "bidirectional"))
    )
    (net (code "39") (name "PWM3") (class "Default")
      (node (ref "Q6") (pin "1") (pinfunction "G_1") (pintype "passive"))
      (node (ref "R28") (pin "1") (pinfunction "1_1") (pintype "passive"))
      (node (ref "R8") (pin "1") (pinfunction "1_1") (pintype "passive"))
      (node (ref "U3") (pin "15") (pinfunction "PB1(OC1A)_15") (pintype "bidirectional"))
    )
    (net (code "40") (name "PWM4") (class "Default")
      (node (ref "Q7") (pin "1") (pinfunction "G_1") (pintype "passive"))
      (node (ref "R29") (pin "1") (pinfunction "1_1") (pintype "passive"))
      (node (ref "R9") (pin "1") (pinfunction "1_1") (pintype "passive"))
      (node (ref "U3") (pin "16") (pinfunction "PB2(SS/OC1B)_16") (pintype "bidirectional"))
    )
    (net (code "41") (name "RESET") (class "Default")
      (node (ref "C5") (pin "1") (pinfunction "1_1") (pintype "passive"))
      (node (ref "R5") (pin "2") (pinfunction "2_2") (pintype "passive"))
      (node (ref "S1") (pin "1") (pinfunction "1_1") (pintype "passive"))
      (node (ref "S1") (pin "2") (pinfunction "2_2") (pintype "passive"))
      (node (ref "U3") (pin "1") (pinfunction "PC6(/RESET)_1") (pintype "bidirectional"))
    )
    (net (code "42") (name "RX") (class "Default")
      (node (ref "JP_SERIAL") (pin "3") (pinfunction "TXO_3") (pintype "passive"))
      (node (ref "Q3") (pin "3") (pinfunction "D_3") (pintype "passive"))
      (node (ref "R17") (pin "1") (pinfunction "1_1") (pintype "passive"))
      (node (ref "R3") (pin "1") (pinfunction "1_1") (pintype "passive"))
      (node (ref "U3") (pin "2") (pinfunction "PD0(RXD)_2") (pintype "bidirectional"))
    )
    (net (code "43") (name "RX_3V3") (class "Default")
      (node (ref "Q3") (pin "2") (pinfunction "S_2") (pintype "passive"))
      (node (ref "R10") (pin "2") (pinfunction "2_2") (pintype "passive"))
      (node (ref "R16") (pin "1") (pinfunction "1_1") (pintype "passive"))
    )
    (net (code "44") (name "SCK") (class "Default")
      (node (ref "J6") (pin "3") (pinfunction "3_3") (pintype "passive"))
      (node (ref "U3") (pin "19") (pinfunction "PB5(SCK)_19") (pintype "bidirectional"))
    )
    (net (code "45") (name "SCL") (class "Default")
      (node (ref "JP_LCD") (pin "1") (pinfunction "1_1") (pintype "passive"))
      (node (ref "R11") (pin "2") (pinfunction "2_2") (pintype "passive"))
      (node (ref "U3") (pin "28") (pinfunction "PC5(ADC5/SCL)_28") (pintype "bidirectional"))
    )
    (net (code "46") (name "SCL_3V3") (class "Default")
      (node (ref "JP_RTC") (pin "3") (pinfunction "3_3") (pintype "passive"))
      (node (ref "K1") (pin "5") (pinfunction "5_5") (pintype "passive"))
    )
    (net (code "47") (name "SDA") (class "Default")
      (node (ref "JP_LCD") (pin "2") (pinfunction "2_2") (pintype "passive"))
      (node (ref "R12") (pin "2") (pinfunction "2_2") (pintype "passive"))
      (node (ref "U3") (pin "27") (pinfunction "PC4(ADC4/SDA)_27") (pintype "bidirectional"))
    )
    (net (code "48") (name "SDA_3V3") (class "Default")
      (node (ref "JP_RTC") (pin "4") (pinfunction "4_4") (pintype "passive"))
      (node (ref "K1") (pin "3") (pinfunction "3_3") (pintype "passive"))
    )
    (net (code "49") (name "TX") (class "Default")
      (node (ref "JP_SERIAL") (pin "2") (pinfunction "RXI_2") (pintype "passive"))
      (node (ref "Q2") (pin "3") (pinfunction "D_3") (pintype "passive"))
      (node (ref "R15") (pin "1") (pinfunction "1_1") (pintype "passive"))
      (node (ref "R4") (pin "1") (pinfunction "1_1") (pintype "passive"))
      (node (ref "U3") (pin "3") (pinfunction "PD1(TXD)_3") (pintype "bidirectional"))
    )
    (net (code "50") (name "TX_3V3") (class "Default")
      (node (ref "Q2") (pin "2") (pinfunction "S_2") (pintype "passive"))
      (node (ref "R13") (pin "2") (pinfunction "2_2") (pintype "passive"))
      (node (ref "R14") (pin "1") (pinfunction "1_1") (pintype "passive"))
    )
    (net (code "51") (name "VCC") (class "Default")
      (node (ref "C3") (pin "1") (pinfunction "+_1") (pintype "passive"))
      (node (ref "F2") (pin "2") (pinfunction "2_2") (pintype "passive"))
      (node (ref "J1") (pin "1") (pinfunction "1_1") (pintype "passive"))
      (node (ref "J1") (pin "2") (pinfunction "2_2") (pintype "passive"))
      (node (ref "J2") (pin "1") (pinfunction "1_1") (pintype "passive"))
      (node (ref "J2") (pin "2") (pinfunction "2_2") (pintype "passive"))
      (node (ref "J3") (pin "1") (pinfunction "1_1") (pintype "passive"))
      (node (ref "J3") (pin "2") (pinfunction "2_2") (pintype "passive"))
      (node (ref "J4") (pin "1") (pinfunction "1_1") (pintype "passive"))
      (node (ref "J4") (pin "2") (pinfunction "2_2") (pintype "passive"))
      (node (ref "JP1") (pin "1") (pinfunction "1_1") (pintype "passive"))
      (node (ref "JP2") (pin "1") (pinfunction "1_1") (pintype "passive"))
      (node (ref "JP3") (pin "1") (pinfunction "1_1") (pintype "passive"))
      (node (ref "JP4") (pin "1") (pinfunction "1_1") (pintype "passive"))
      (node (ref "JP5") (pin "4") (pinfunction "4_4") (pintype "passive"))
      (node (ref "U2") (pin "1") (pinfunction "IN_1") (pintype "bidirectional"))
    )
    (net (code "52") (name "unconnected-(J6-Pad5)") (class "Default")
      (node (ref "J6") (pin "5") (pinfunction "5_5") (pintype "passive"))
    )
    (net (code "53") (name "unconnected-(JP_RTC-Pad2)") (class "Default")
      (node (ref "JP_RTC") (pin "2") (pinfunction "2_2") (pintype "passive"))
    )
    (net (code "54") (name "unconnected-(JP_SERIAL-CTS-Pad5)") (class "Default")
      (node (ref "JP_SERIAL") (pin "5") (pinfunction "CTS_5") (pintype "passive"))
    )
    (net (code "55") (name "unconnected-(K1-Pad7)") (class "Default")
      (node (ref "K1") (pin "7") (pinfunction "7_7") (pintype "passive"))
    )
    (net (code "56") (name "unconnected-(K1-Pad11)") (class "Default")
      (node (ref "K1") (pin "11") (pinfunction "11_11") (pintype "passive"))
    )
    (net (code "57") (name "unconnected-(K1-Pad12)") (class "Default")
      (node (ref "K1") (pin "12") (pinfunction "12_12") (pintype "passive"))
    )
    (net (code "58") (name "unconnected-(K1-Pad13)") (class "Default")
      (node (ref "K1") (pin "13") (pinfunction "13_13") (pintype "passive"))
    )
    (net (code "59") (name "unconnected-(K1-Pad15)") (class "Default")
      (node (ref "K1") (pin "15") (pinfunction "15_15") (pintype "passive"))
    )
    (net (code "60") (name "unconnected-(K1-Pad16)") (class "Default")
      (node (ref "K1") (pin "16") (pinfunction "16_16") (pintype "passive"))
    )
    (net (code "61") (name "unconnected-(K1-Pad18)") (class "Default")
      (node (ref "K1") (pin "18") (pinfunction "18_18") (pintype "passive"))
    )
    (net (code "62") (name "unconnected-(K1-Pad19)") (class "Default")
      (node (ref "K1") (pin "19") (pinfunction "19_19") (pintype "passive"))
    )
    (net (code "63") (name "unconnected-(K1-Pad21)") (class "Default")
      (node (ref "K1") (pin "21") (pinfunction "21_21") (pintype "passive"))
    )
    (net (code "64") (name "unconnected-(K1-Pad22)") (class "Default")
      (node (ref "K1") (pin "22") (pinfunction "22_22") (pintype "passive"))
    )
    (net (code "65") (name "unconnected-(K1-Pad23)") (class "Default")
      (node (ref "K1") (pin "23") (pinfunction "23_23") (pintype "passive"))
    )
    (net (code "66") (name "unconnected-(K1-Pad24)") (class "Default")
      (node (ref "K1") (pin "24") (pinfunction "24_24") (pintype "passive"))
    )
    (net (code "67") (name "unconnected-(K1-Pad26)") (class "Default")
      (node (ref "K1") (pin "26") (pinfunction "26_26") (pintype "passive"))
    )
    (net (code "68") (name "unconnected-(K1-Pad27)") (class "Default")
      (node (ref "K1") (pin "27") (pinfunction "27_27") (pintype "passive"))
    )
    (net (code "69") (name "unconnected-(K1-Pad28)") (class "Default")
      (node (ref "K1") (pin "28") (pinfunction "28_28") (pintype "passive"))
    )
    (net (code "70") (name "unconnected-(K1-Pad29)") (class "Default")
      (node (ref "K1") (pin "29") (pinfunction "29_29") (pintype "passive"))
    )
    (net (code "71") (name "unconnected-(K1-Pad31)") (class "Default")
      (node (ref "K1") (pin "31") (pinfunction "31_31") (pintype "passive"))
    )
    (net (code "72") (name "unconnected-(K1-Pad32)") (class "Default")
      (node (ref "K1") (pin "32") (pinfunction "32_32") (pintype "passive"))
    )
    (net (code "73") (name "unconnected-(K1-Pad33)") (class "Default")
      (node (ref "K1") (pin "33") (pinfunction "33_33") (pintype "passive"))
    )
    (net (code "74") (name "unconnected-(K1-Pad35)") (class "Default")
      (node (ref "K1") (pin "35") (pinfunction "35_35") (pintype "passive"))
    )
    (net (code "75") (name "unconnected-(K1-Pad36)") (class "Default")
      (node (ref "K1") (pin "36") (pinfunction "36_36") (pintype "passive"))
    )
    (net (code "76") (name "unconnected-(K1-Pad37)") (class "Default")
      (node (ref "K1") (pin "37") (pinfunction "37_37") (pintype "passive"))
    )
    (net (code "77") (name "unconnected-(K1-Pad38)") (class "Default")
      (node (ref "K1") (pin "38") (pinfunction "38_38") (pintype "passive"))
    )
    (net (code "78") (name "unconnected-(K1-Pad40)") (class "Default")
      (node (ref "K1") (pin "40") (pinfunction "40_40") (pintype "passive"))
    )
    (net (code "79") (name "unconnected-(U3-AREF-Pad21)") (class "Default")
      (node (ref "U3") (pin "21") (pinfunction "AREF_21") (pintype "bidirectional"))
    )
    (net (code "80") (name "unconnected-(U3-PC0(ADC0)-Pad23)") (class "Default")
      (node (ref "U3") (pin "23") (pinfunction "PC0(ADC0)_23") (pintype "bidirectional"))
    )
    (net (code "81") (name "unconnected-(U3-PC1(ADC1)-Pad24)") (class "Default")
      (node (ref "U3") (pin "24") (pinfunction "PC1(ADC1)_24") (pintype "bidirectional"))
    )
    (net (code "82") (name "unconnected-(U3-PC2(ADC2)-Pad25)") (class "Default")
      (node (ref "U3") (pin "25") (pinfunction "PC2(ADC2)_25") (pintype "bidirectional"))
    )
    (net (code "83") (name "unconnected-(U3-PC3(ADC3)-Pad26)") (class "Default")
      (node (ref "U3") (pin "26") (pinfunction "PC3(ADC3)_26") (pintype "bidirectional"))
    )
    (net (code "84") (name "unconnected-(X1-Pad2)") (class "Default")
      (node (ref "X1") (pin "2") (pinfunction "2_2") (pintype "passive"))
    )
    (net (code "85") (name "unconnected-(X1-Pad3)") (class "Default")
      (node (ref "X1") (pin "3") (pinfunction "3_3") (pintype "passive"))
    )
  )
)
